# PPM_USB.net
KiCad netlist of a schematic drawn in Altium Designer
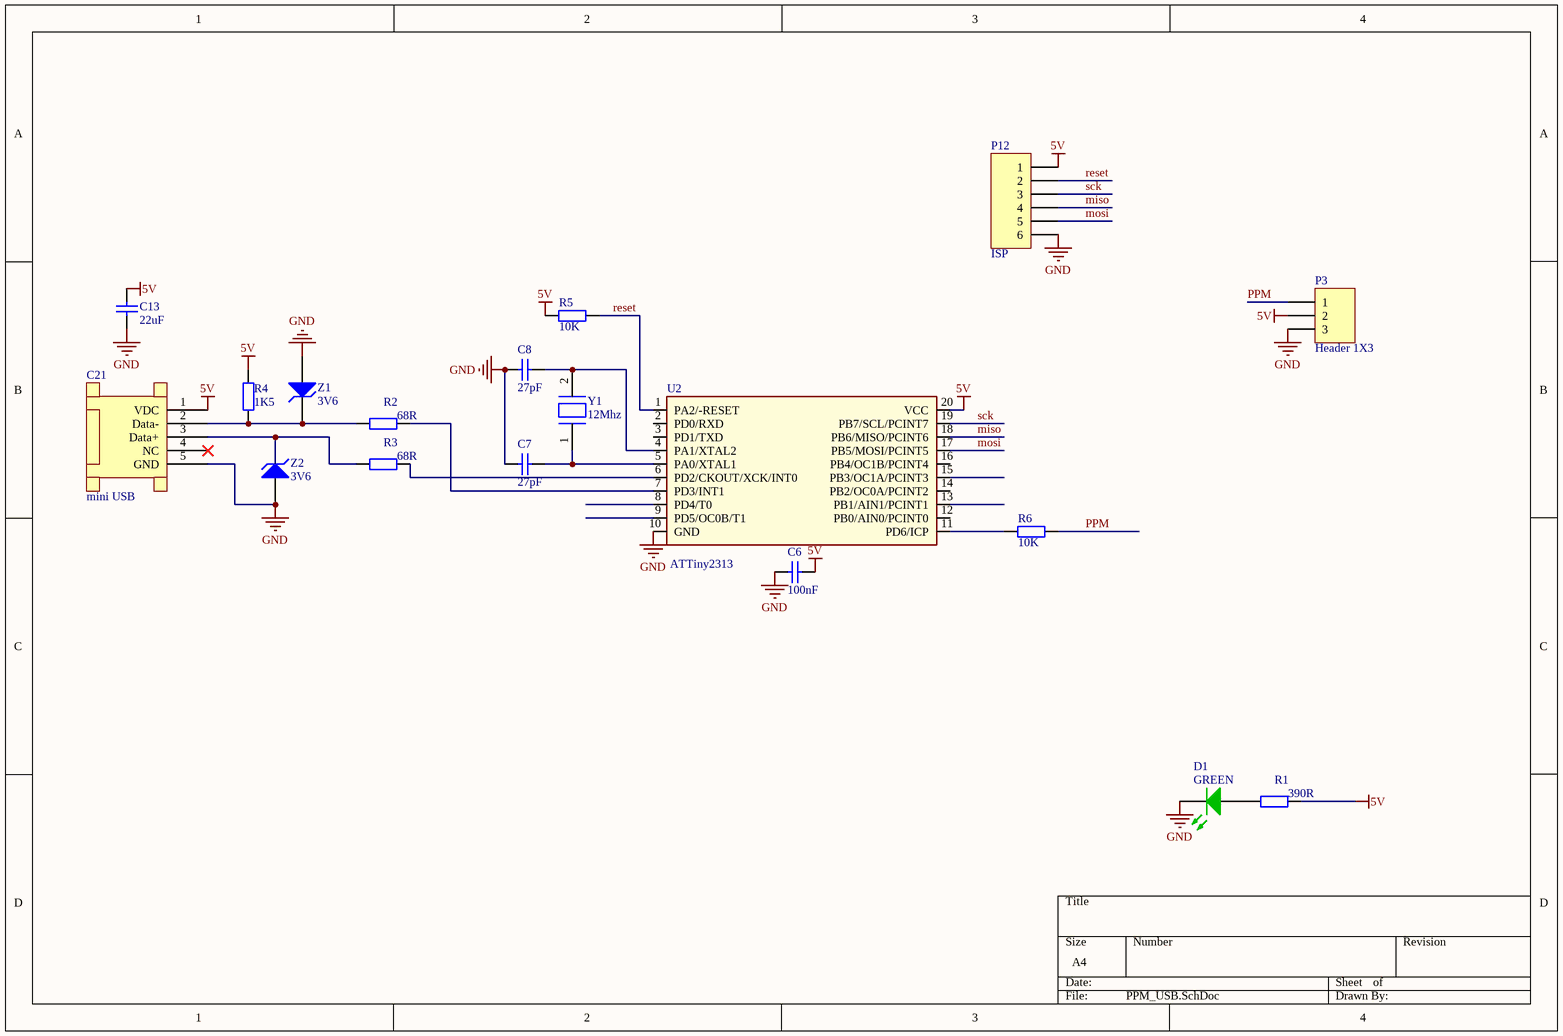
[diagram p0: PPM_USB.SchDoc]

(export (version "E")
  (design (tool "Eeschema 10.0.6"))
  (components
    (comp (ref "C6")
      (value "100nF")
      (footprint "FP_0603_CAP_080")
      (description "Capacitor")
      (libsource (lib "Capacitor") (part "CAP"))
    )
    (comp (ref "C7")
      (value "27pF")
      (footprint "FP_0603_CAP_080")
      (description "Capacitor")
      (libsource (lib "Capacitor") (part "CAP"))
    )
    (comp (ref "C8")
      (value "27pF")
      (footprint "FP_0603_CAP_080")
      (description "Capacitor")
      (libsource (lib "Capacitor") (part "CAP"))
    )
    (comp (ref "C13")
      (value "22uF")
      (footprint "FP_0805_CAP_085")
      (description "Capacitor")
      (libsource (lib "Capacitor") (part "CAP"))
    )
    (comp (ref "C21")
      (value "mini USB")
      (footprint "USB/SM0.8-6H5")
      (libsource (lib "mini USB") (part "mini USB"))
    )
    (comp (ref "D1")
      (value "GREEN")
      (footprint "FP_0603_LED_G")
      (description "Typical LED")
      (libsource (lib "Led_optical") (part "LED_G"))
    )
    (comp (ref "P3")
      (value "Header 1X3")
      (footprint "HEADER_2.54MM_M_1x3")
      (description "Header, 3-Pin")
      (libsource (lib "Header") (part "Header 1X3"))
    )
    (comp (ref "P12")
      (value "ISP")
      (footprint "HEADER_2.00MM_M_1x6")
      (description "Header, 6-Pin")
      (fields (field (name "PUBLISHER") "Altium Limited"))
      (libsource (lib "Miscellaneous Connectors") (part "Header 6"))
    )
    (comp (ref "R1")
      (value "390R")
      (footprint "FP_0603_RES")
      (description "Resistor")
      (libsource (lib "") (part "RES_1"))
    )
    (comp (ref "R2")
      (value "68R")
      (footprint "FP_0603_RES")
      (description "Resistor")
      (libsource (lib "") (part "RES_1"))
    )
    (comp (ref "R3")
      (value "68R")
      (footprint "FP_0603_RES")
      (description "Resistor")
      (libsource (lib "") (part "RES_1"))
    )
    (comp (ref "R4")
      (value "1K5")
      (footprint "FP_0603_RES")
      (description "Resistor")
      (libsource (lib "") (part "RES_2"))
    )
    (comp (ref "R5")
      (value "10K")
      (footprint "FP_0603_RES")
      (description "Resistor")
      (libsource (lib "Resistor") (part "RES"))
    )
    (comp (ref "R6")
      (value "10K")
      (footprint "FP_0603_RES")
      (description "Resistor")
      (libsource (lib "Resistor") (part "RES"))
    )
    (comp (ref "U2")
      (value "ATTiny2313")
      (footprint "DIGITAL_SOIC20W")
      (libsource (lib "uC") (part "ATTiny2313"))
    )
    (comp (ref "Y1")
      (value "12Mhz")
      (footprint "FP_CRYSTAL_HC49_TH")
      (description "Quartz")
      (libsource (lib "Quartz") (part "XTAL"))
    )
    (comp (ref "Z1")
      (value "3V6")
      (footprint "FP_SOD-123")
      (description "Zener Diode")
      (libsource (lib "Diode") (part "ZENER"))
    )
    (comp (ref "Z2")
      (value "3V6")
      (footprint "FP_SOD-123")
      (description "Zener Diode")
      (libsource (lib "Diode") (part "ZENER"))
    )
  )
  (nets
    (net (code "1") (name "/PPM") (class "Default")
      (node (ref "P3") (pin "1") (pinfunction "1_1") (pintype "passive"))
      (node (ref "R6") (pin "2") (pinfunction "2_2") (pintype "passive"))
    )
    (net (code "2") (name "/miso") (class "Default")
      (node (ref "P12") (pin "4") (pinfunction "4_4") (pintype "passive"))
      (node (ref "U2") (pin "18") (pinfunction "PB6/MISO/PCINT6_18") (pintype "passive"))
    )
    (net (code "3") (name "/mosi") (class "Default")
      (node (ref "P12") (pin "5") (pinfunction "5_5") (pintype "passive"))
      (node (ref "U2") (pin "17") (pinfunction "PB5/MOSI/PCINT5_17") (pintype "passive"))
    )
    (net (code "4") (name "/reset") (class "Default")
      (node (ref "P12") (pin "2") (pinfunction "2_2") (pintype "passive"))
      (node (ref "R5") (pin "2") (pinfunction "2_2") (pintype "passive"))
      (node (ref "U2") (pin "1") (pinfunction "PA2/-RESET_1") (pintype "passive"))
    )
    (net (code "5") (name "/sck") (class "Default")
      (node (ref "P12") (pin "3") (pinfunction "3_3") (pintype "passive"))
      (node (ref "U2") (pin "19") (pinfunction "PB7/SCL/PCINT7_19") (pintype "passive"))
    )
    (net (code "6") (name "5V") (class "Default")
      (node (ref "C13") (pin "2") (pinfunction "2_2") (pintype "passive"))
      (node (ref "C21") (pin "1") (pinfunction "VDC_1") (pintype "passive"))
      (node (ref "C6") (pin "2") (pinfunction "2_2") (pintype "passive"))
      (node (ref "P12") (pin "1") (pinfunction "1_1") (pintype "passive"))
      (node (ref "P3") (pin "2") (pinfunction "2_2") (pintype "passive"))
      (node (ref "R1") (pin "1") (pinfunction "1_1") (pintype "passive"))
      (node (ref "R4") (pin "1") (pinfunction "1_1") (pintype "passive"))
      (node (ref "R5") (pin "1") (pinfunction "1_1") (pintype "passive"))
      (node (ref "U2") (pin "20") (pinfunction "VCC_20") (pintype "passive"))
    )
    (net (code "7") (name "GND") (class "Default")
      (node (ref "C13") (pin "1") (pinfunction "1_1") (pintype "passive"))
      (node (ref "C21") (pin "5") (pinfunction "GND_5") (pintype "passive"))
      (node (ref "C6") (pin "1") (pinfunction "1_1") (pintype "passive"))
      (node (ref "C7") (pin "1") (pinfunction "1_1") (pintype "passive"))
      (node (ref "C8") (pin "1") (pinfunction "1_1") (pintype "passive"))
      (node (ref "D1") (pin "K") (pinfunction "K_K") (pintype "passive"))
      (node (ref "P12") (pin "6") (pinfunction "6_6") (pintype "passive"))
      (node (ref "P3") (pin "3") (pinfunction "3_3") (pintype "passive"))
      (node (ref "U2") (pin "10") (pinfunction "GND_10") (pintype "passive"))
      (node (ref "Z1") (pin "A") (pinfunction "A_A") (pintype "passive"))
      (node (ref "Z2") (pin "A") (pinfunction "A_A") (pintype "passive"))
    )
    (net (code "8") (name "Net-(C21-Data+)") (class "Default")
      (node (ref "C21") (pin "3") (pinfunction "Data+_3") (pintype "passive"))
      (node (ref "R3") (pin "2") (pinfunction "2_2") (pintype "passive"))
      (node (ref "Z2") (pin "K") (pinfunction "K_K") (pintype "passive"))
    )
    (net (code "9") (name "Net-(C21-Data-)") (class "Default")
      (node (ref "C21") (pin "2") (pinfunction "Data-_2") (pintype "passive"))
      (node (ref "R2") (pin "2") (pinfunction "2_2") (pintype "passive"))
      (node (ref "R4") (pin "2") (pinfunction "2_2") (pintype "passive"))
      (node (ref "Z1") (pin "K") (pinfunction "K_K") (pintype "passive"))
    )
    (net (code "10") (name "Net-(D1-PadA)") (class "Default")
      (node (ref "D1") (pin "A") (pinfunction "A_A") (pintype "passive"))
      (node (ref "R1") (pin "2") (pinfunction "2_2") (pintype "passive"))
    )
    (net (code "11") (name "Net-(U2-PA0{slash}XTAL1)") (class "Default")
      (node (ref "C7") (pin "2") (pinfunction "2_2") (pintype "passive"))
      (node (ref "U2") (pin "5") (pinfunction "PA0/XTAL1_5") (pintype "passive"))
      (node (ref "Y1") (pin "1") (pinfunction "1_1") (pintype "passive"))
    )
    (net (code "12") (name "Net-(U2-PA1{slash}XTAL2)") (class "Default")
      (node (ref "C8") (pin "2") (pinfunction "2_2") (pintype "passive"))
      (node (ref "U2") (pin "4") (pinfunction "PA1/XTAL2_4") (pintype "passive"))
      (node (ref "Y1") (pin "2") (pinfunction "2_2") (pintype "passive"))
    )
    (net (code "13") (name "Net-(U2-PD2{slash}CKOUT{slash}XCK{slash}INT0)") (class "Default")
      (node (ref "R3") (pin "1") (pinfunction "1_1") (pintype "passive"))
      (node (ref "U2") (pin "6") (pinfunction "PD2/CKOUT/XCK/INT0_6") (pintype "passive"))
    )
    (net (code "14") (name "Net-(U2-PD3{slash}INT1)") (class "Default")
      (node (ref "R2") (pin "1") (pinfunction "1_1") (pintype "passive"))
      (node (ref "U2") (pin "7") (pinfunction "PD3/INT1_7") (pintype "passive"))
    )
    (net (code "15") (name "Net-(U2-PD6{slash}ICP)") (class "Default")
      (node (ref "R6") (pin "1") (pinfunction "1_1") (pintype "passive"))
      (node (ref "U2") (pin "11") (pinfunction "PD6/ICP_11") (pintype "passive"))
    )
    (net (code "16") (name "unconnected-(C21-NC-Pad4)") (class "Default")
      (node (ref "C21") (pin "4") (pinfunction "NC_4") (pintype "passive+no_connect"))
    )
    (net (code "17") (name "unconnected-(U2-PB0{slash}AIN0{slash}PCINT0-Pad12)") (class "Default")
      (node (ref "U2") (pin "12") (pinfunction "PB0/AIN0/PCINT0_12") (pintype "passive"))
    )
    (net (code "18") (name "unconnected-(U2-PB1{slash}AIN1{slash}PCINT1-Pad13)") (class "Default")
      (node (ref "U2") (pin "13") (pinfunction "PB1/AIN1/PCINT1_13") (pintype "passive"))
    )
    (net (code "19") (name "unconnected-(U2-PB2{slash}OC0A{slash}PCINT2-Pad14)") (class "Default")
      (node (ref "U2") (pin "14") (pinfunction "PB2/OC0A/PCINT2_14") (pintype "passive"))
    )
    (net (code "20") (name "unconnected-(U2-PB3{slash}OC1A{slash}PCINT3-Pad15)") (class "Default")
      (node (ref "U2") (pin "15") (pinfunction "PB3/OC1A/PCINT3_15") (pintype "passive"))
    )
    (net (code "21") (name "unconnected-(U2-PB4{slash}OC1B{slash}PCINT4-Pad16)") (class "Default")
      (node (ref "U2") (pin "16") (pinfunction "PB4/OC1B/PCINT4_16") (pintype "passive"))
    )
    (net (code "22") (name "unconnected-(U2-PD0{slash}RXD-Pad2)") (class "Default")
      (node (ref "U2") (pin "2") (pinfunction "PD0/RXD_2") (pintype "passive"))
    )
    (net (code "23") (name "unconnected-(U2-PD1{slash}TXD-Pad3)") (class "Default")
      (node (ref "U2") (pin "3") (pinfunction "PD1/TXD_3") (pintype "passive"))
    )
    (net (code "24") (name "unconnected-(U2-PD4{slash}T0-Pad8)") (class "Default")
      (node (ref "U2") (pin "8") (pinfunction "PD4/T0_8") (pintype "passive"))
    )
    (net (code "25") (name "unconnected-(U2-PD5{slash}OC0B{slash}T1-Pad9)") (class "Default")
      (node (ref "U2") (pin "9") (pinfunction "PD5/OC0B/T1_9") (pintype "passive"))
    )
  )
)
